# Printrhub_Rev_0_3.net
KiCad netlist of a schematic drawn in EAGLE
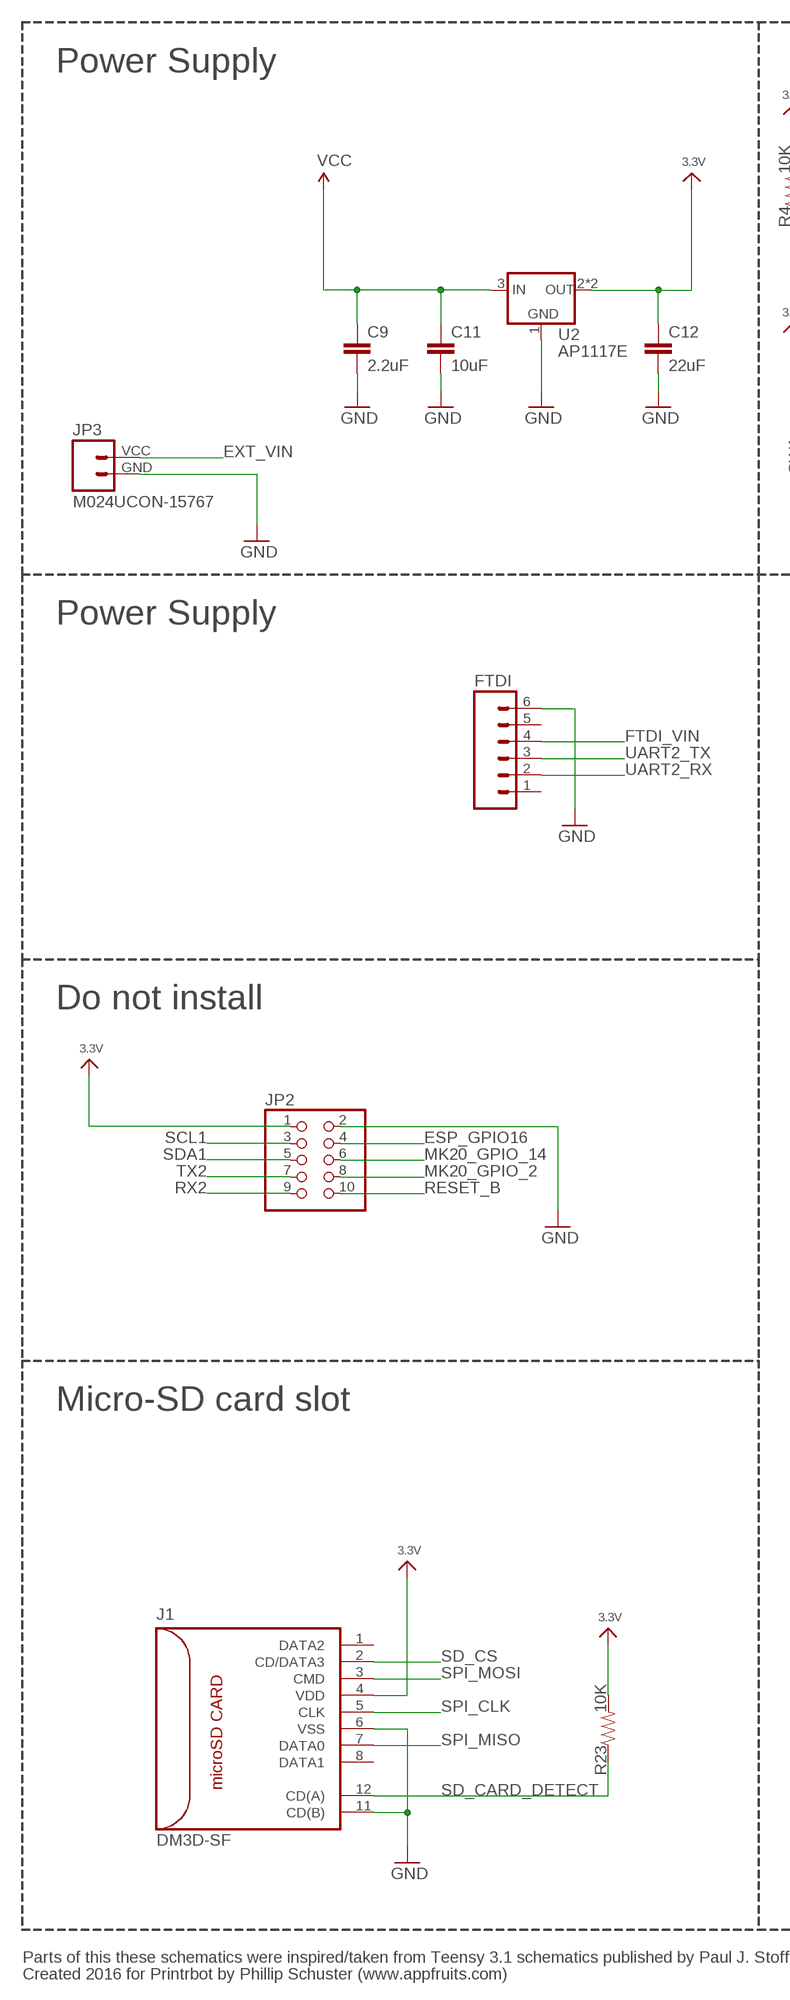
[diagram p0: schematic, sheet 1, part 1 of 2]
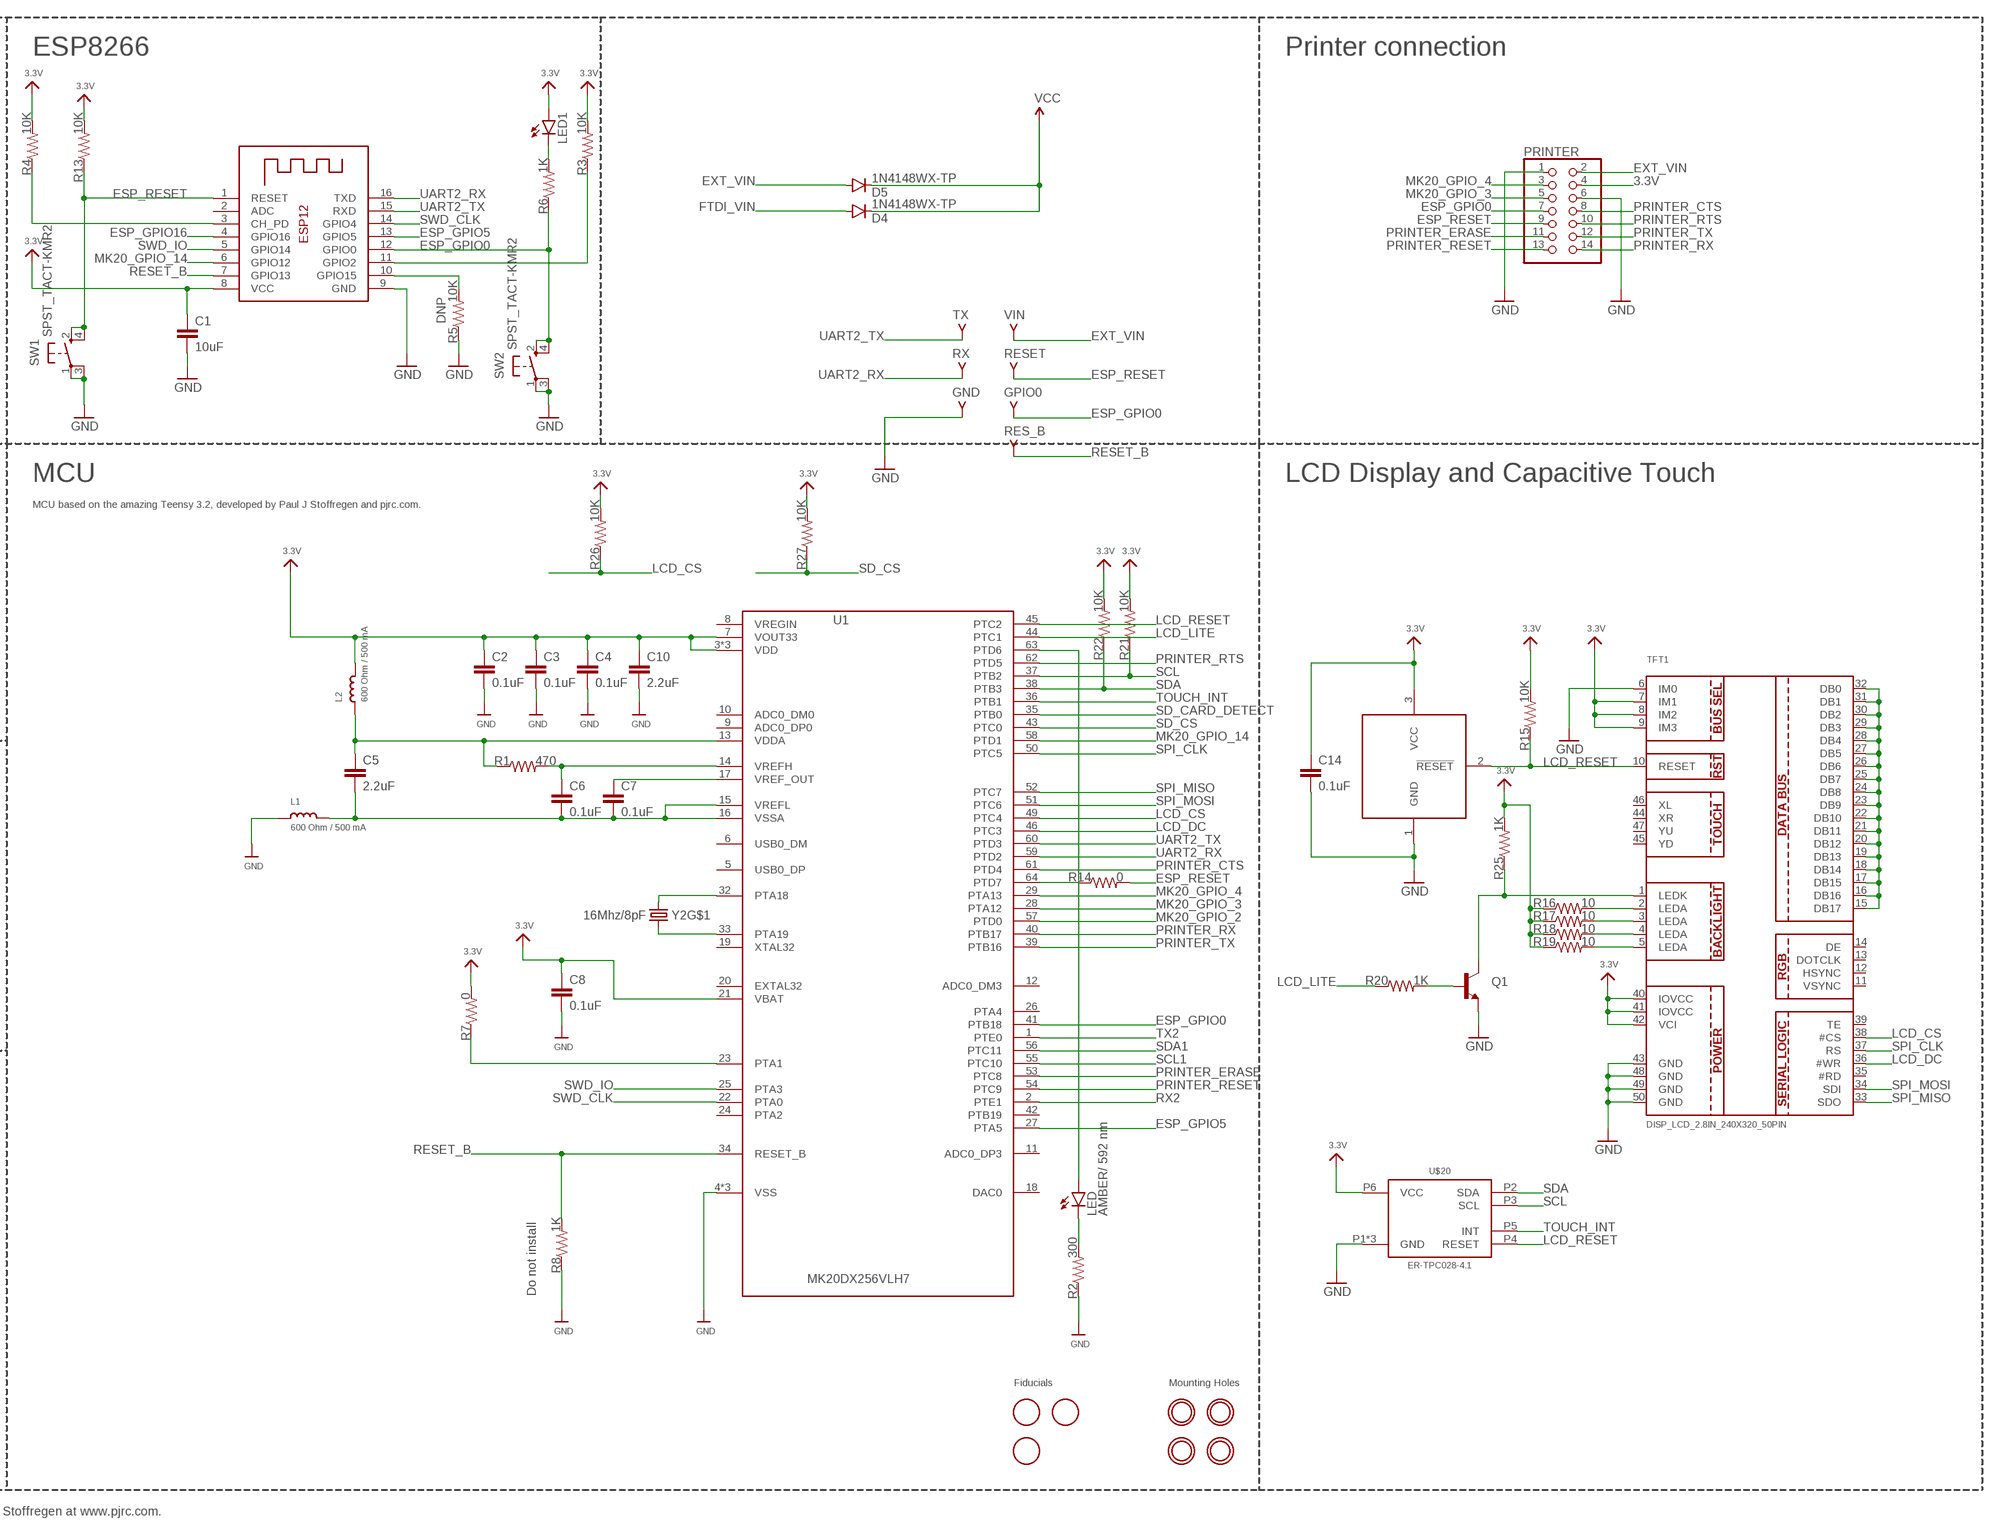
[diagram p1: schematic, sheet 1, part 2 of 2]

(export (version "E")
  (design (tool "Eeschema 10.0.6"))
  (components
    (comp (ref "C1")
      (value "10uF")
      (footprint "eagle-import:0603-CAP")
      (fields (field (name "MF") "Murata") (field (name "MPN") "GRM188R60J106ME47D"))
      (libsource (lib "eagle-import") (part "CAPACITOR-10UF"))
    )
    (comp (ref "C2")
      (value "0.1uF")
      (footprint "eagle-import:0603-CAP")
      (fields (field (name "MF") "Kemet") (field (name "MPN") "C0603C104J3RACTU"))
      (libsource (lib "eagle-import") (part "CAPACITOR-0.1UF"))
    )
    (comp (ref "C3")
      (value "0.1uF")
      (footprint "eagle-import:0603-CAP")
      (fields (field (name "MF") "Kemet") (field (name "MPN") "C0603C104J3RACTU"))
      (libsource (lib "eagle-import") (part "CAPACITOR-0.1UF"))
    )
    (comp (ref "C4")
      (value "0.1uF")
      (footprint "eagle-import:0603-CAP")
      (fields (field (name "MF") "Kemet") (field (name "MPN") "C0603C104J3RACTU"))
      (libsource (lib "eagle-import") (part "CAPACITOR-0.1UF"))
    )
    (comp (ref "C5")
      (value "2.2uF")
      (footprint "eagle-import:0603-CAP")
      (fields (field (name "MF") "Kemet") (field (name "MPN") "C0603C225K4PACTU"))
      (libsource (lib "eagle-import") (part "CAPACITOR-2.2UF"))
    )
    (comp (ref "C6")
      (value "0.1uF")
      (footprint "eagle-import:0603-CAP")
      (fields (field (name "MF") "Kemet") (field (name "MPN") "C0603C104J3RACTU"))
      (libsource (lib "eagle-import") (part "CAPACITOR-0.1UF"))
    )
    (comp (ref "C7")
      (value "0.1uF")
      (footprint "eagle-import:0603-CAP")
      (fields (field (name "MF") "Kemet") (field (name "MPN") "C0603C104J3RACTU"))
      (libsource (lib "eagle-import") (part "CAPACITOR-0.1UF"))
    )
    (comp (ref "C8")
      (value "0.1uF")
      (footprint "eagle-import:0603-CAP")
      (fields (field (name "MF") "Kemet") (field (name "MPN") "C0603C104J3RACTU"))
      (libsource (lib "eagle-import") (part "CAPACITOR-0.1UF"))
    )
    (comp (ref "C9")
      (value "2.2uF")
      (footprint "eagle-import:0603-CAP")
      (fields (field (name "MF") "Kemet") (field (name "MPN") "C0603C225K4PACTU"))
      (libsource (lib "eagle-import") (part "CAPACITOR-2.2UF"))
    )
    (comp (ref "C10")
      (value "2.2uF")
      (footprint "eagle-import:0603-CAP")
      (fields (field (name "MF") "Kemet") (field (name "MPN") "C0603C225K4PACTU"))
      (libsource (lib "eagle-import") (part "CAPACITOR-2.2UF"))
    )
    (comp (ref "C11")
      (value "10uF")
      (footprint "eagle-import:0603-CAP")
      (fields (field (name "MF") "Murata") (field (name "MPN") "GRM188R60J106ME47D"))
      (libsource (lib "eagle-import") (part "CAPACITOR-10UF"))
    )
    (comp (ref "C12")
      (value "22uF")
      (footprint "eagle-import:0603-CAP")
      (fields (field (name "MF") "Murata") (field (name "MPN") "GRM188R60J226MEA0D"))
      (libsource (lib "eagle-import") (part "CAPACITOR-22UF"))
    )
    (comp (ref "C14")
      (value "0.1uF")
      (footprint "eagle-import:0603-CAP")
      (fields (field (name "MF") "Kemet") (field (name "MPN") "C0603C104J3RACTU"))
      (libsource (lib "eagle-import") (part "CAPACITOR-0.1UF"))
    )
    (comp (ref "D4")
      (value "1N4148WX-TP")
      (footprint "eagle-import:SOD-323")
      (fields (field (name "MF") "Micro Commercial Co"))
      (libsource (lib "eagle-import") (part "DIODESOD"))
    )
    (comp (ref "D5")
      (value "1N4148WX-TP")
      (footprint "eagle-import:SOD-323")
      (fields (field (name "MF") "Micro Commercial Co"))
      (libsource (lib "eagle-import") (part "DIODESOD"))
    )
    (comp (ref "FTDI")
      (value "M06SMD-STRAIGHT-ALT")
      (footprint "eagle-import:1X06_SMD_STRAIGHT_ALT")
      (libsource (lib "eagle-import") (part "M06SMD-STRAIGHT-ALT"))
    )
    (comp (ref "GND")
      (value "TPV-SMD-18RN")
      (footprint "eagle-import:SMD-18RN")
      (libsource (lib "eagle-import") (part "TPV-SMD-18RN"))
    )
    (comp (ref "GPIO0")
      (value "TPV-SMD-18RN")
      (footprint "eagle-import:SMD-18RN")
      (libsource (lib "eagle-import") (part "TPV-SMD-18RN"))
    )
    (comp (ref "J1")
      (value "DM3D-SF")
      (footprint "eagle-import:DM3D-SF")
      (libsource (lib "eagle-import") (part "DM3D-SF"))
    )
    (comp (ref "JP2")
      (value "PINHD-2X5SMT")
      (footprint "eagle-import:2X05_SMT")
      (libsource (lib "eagle-import") (part "PINHD-2X5SMT"))
    )
    (comp (ref "JP3")
      (value "M024UCON-15767")
      (footprint "eagle-import:JST-2-SMD-VERT")
      (libsource (lib "eagle-import") (part "M024UCON-15767"))
    )
    (comp (ref "L1")
      (value "600 Ohm / 500 mA")
      (footprint "eagle-import:0603")
      (fields (field (name "MF") "Murata") (field (name "MPN") "BLM18AG601SN1D"))
      (libsource (lib "eagle-import") (part "INDUCTOR-0603_600OHM/500MA"))
    )
    (comp (ref "L2")
      (value "600 Ohm / 500 mA")
      (footprint "eagle-import:0603")
      (fields (field (name "MF") "Murata") (field (name "MPN") "BLM18AG601SN1D"))
      (libsource (lib "eagle-import") (part "INDUCTOR-0603_600OHM/500MA"))
    )
    (comp (ref "LED")
      (value "AMBER/ 592 nm")
      (footprint "eagle-import:LED-0603")
      (fields (field (name "MF") "Avago Technologies") (field (name "MPN") "HSMA-C190"))
      (libsource (lib "eagle-import") (part "LED-AMBER"))
    )
    (comp (ref "LED1")
      (value "LED-GREEN")
      (footprint "eagle-import:LED-0603")
      (fields (field (name "MF") "Avago") (field (name "MPN") "HSMG-C190"))
      (libsource (lib "eagle-import") (part "LED-GREEN"))
    )
    (comp (ref "PRINTER")
      (value "PINHD-2X7SMT")
      (footprint "eagle-import:2X07_SMT")
      (libsource (lib "eagle-import") (part "PINHD-2X7SMT"))
    )
    (comp (ref "Q1")
      (value "TRANSISTOR_NPNSOT23-3")
      (footprint "eagle-import:SOT23-3")
      (fields (field (name "MF") "ON Semiconductor") (field (name "MPN") "MMBT2222ALT1G"))
      (libsource (lib "eagle-import") (part "TRANSISTOR_NPNSOT23-3"))
    )
    (comp (ref "R1")
      (value "470")
      (footprint "eagle-import:0603-RES")
      (fields (field (name "MF") "Panasonic") (field (name "MPN") "ERJ-3GEYJ471V"))
      (libsource (lib "eagle-import") (part "RESISTOR-470"))
    )
    (comp (ref "R2")
      (value "300")
      (footprint "eagle-import:0603-RES")
      (libsource (lib "eagle-import") (part "RESISTOR0603"))
    )
    (comp (ref "R3")
      (value "10K")
      (footprint "eagle-import:0603-RES")
      (fields (field (name "MF") "Panasonic") (field (name "MPN") "ERJ-3GEYJ103V"))
      (libsource (lib "eagle-import") (part "RESISTOR-10K"))
    )
    (comp (ref "R4")
      (value "10K")
      (footprint "eagle-import:0603-RES")
      (fields (field (name "MF") "Panasonic") (field (name "MPN") "ERJ-3GEYJ103V"))
      (libsource (lib "eagle-import") (part "RESISTOR-10K"))
    )
    (comp (ref "R5")
      (value "10K")
      (footprint "eagle-import:0603-RES")
      (fields (field (name "MF") "Panasonic") (field (name "MPN") "ERJ-3GEYJ103V"))
      (libsource (lib "eagle-import") (part "RESISTOR-10K"))
    )
    (comp (ref "R6")
      (value "1K")
      (footprint "eagle-import:0603-RES")
      (fields (field (name "MF") "Panasonic") (field (name "MPN") "ERJ-3GEYJ102V"))
      (libsource (lib "eagle-import") (part "RESISTOR-1K"))
    )
    (comp (ref "R7")
      (value "0")
      (footprint "eagle-import:0603-RES")
      (fields (field (name "MF") "Panasonic") (field (name "MPN") "ERJ-3GEY0R00V"))
      (libsource (lib "eagle-import") (part "RESISTOR-0"))
    )
    (comp (ref "R8")
      (value "1K")
      (footprint "eagle-import:0603-RES")
      (fields (field (name "MF") "Panasonic") (field (name "MPN") "ERJ-3GEYJ102V"))
      (libsource (lib "eagle-import") (part "RESISTOR-1K"))
    )
    (comp (ref "R13")
      (value "10K")
      (footprint "eagle-import:0603-RES")
      (fields (field (name "MF") "Panasonic") (field (name "MPN") "ERJ-3GEYJ103V"))
      (libsource (lib "eagle-import") (part "RESISTOR-10K"))
    )
    (comp (ref "R14")
      (value "0")
      (footprint "eagle-import:0603-RES")
      (fields (field (name "MF") "Panasonic") (field (name "MPN") "ERJ-3GEY0R00V"))
      (libsource (lib "eagle-import") (part "RESISTOR-0"))
    )
    (comp (ref "R15")
      (value "10K")
      (footprint "eagle-import:0603-RES")
      (fields (field (name "MF") "Panasonic") (field (name "MPN") "ERJ-3GEYJ103V"))
      (libsource (lib "eagle-import") (part "RESISTOR-10K"))
    )
    (comp (ref "R16")
      (value "10")
      (footprint "eagle-import:0603-RES")
      (fields (field (name "MF") "Panasonic") (field (name "MPN") "ERJ-3EKF10R0V"))
      (libsource (lib "eagle-import") (part "RESISTOR-10"))
    )
    (comp (ref "R17")
      (value "10")
      (footprint "eagle-import:0603-RES")
      (fields (field (name "MF") "Panasonic") (field (name "MPN") "ERJ-3EKF10R0V"))
      (libsource (lib "eagle-import") (part "RESISTOR-10"))
    )
    (comp (ref "R18")
      (value "10")
      (footprint "eagle-import:0603-RES")
      (fields (field (name "MF") "Panasonic") (field (name "MPN") "ERJ-3EKF10R0V"))
      (libsource (lib "eagle-import") (part "RESISTOR-10"))
    )
    (comp (ref "R19")
      (value "10")
      (footprint "eagle-import:0603-RES")
      (fields (field (name "MF") "Panasonic") (field (name "MPN") "ERJ-3EKF10R0V"))
      (libsource (lib "eagle-import") (part "RESISTOR-10"))
    )
    (comp (ref "R20")
      (value "1K")
      (footprint "eagle-import:0603-RES")
      (fields (field (name "MF") "Panasonic") (field (name "MPN") "ERJ-3GEYJ102V"))
      (libsource (lib "eagle-import") (part "RESISTOR-1K"))
    )
    (comp (ref "R21")
      (value "10K")
      (footprint "eagle-import:0603-RES")
      (fields (field (name "MF") "Panasonic") (field (name "MPN") "ERJ-3GEYJ103V"))
      (libsource (lib "eagle-import") (part "RESISTOR-10K"))
    )
    (comp (ref "R22")
      (value "10K")
      (footprint "eagle-import:0603-RES")
      (fields (field (name "MF") "Panasonic") (field (name "MPN") "ERJ-3GEYJ103V"))
      (libsource (lib "eagle-import") (part "RESISTOR-10K"))
    )
    (comp (ref "R23")
      (value "10K")
      (footprint "eagle-import:0603-RES")
      (fields (field (name "MF") "Panasonic") (field (name "MPN") "ERJ-3GEYJ103V"))
      (libsource (lib "eagle-import") (part "RESISTOR-10K"))
    )
    (comp (ref "R25")
      (value "1K")
      (footprint "eagle-import:0603-RES")
      (fields (field (name "MF") "Panasonic") (field (name "MPN") "ERJ-3GEYJ102V"))
      (libsource (lib "eagle-import") (part "RESISTOR-1K"))
    )
    (comp (ref "R26")
      (value "10K")
      (footprint "eagle-import:0603-RES")
      (fields (field (name "MF") "Panasonic") (field (name "MPN") "ERJ-3GEYJ103V"))
      (libsource (lib "eagle-import") (part "RESISTOR-10K"))
    )
    (comp (ref "R27")
      (value "10K")
      (footprint "eagle-import:0603-RES")
      (fields (field (name "MF") "Panasonic") (field (name "MPN") "ERJ-3GEYJ103V"))
      (libsource (lib "eagle-import") (part "RESISTOR-10K"))
    )
    (comp (ref "RESET")
      (value "TPV-SMD-18RN")
      (footprint "eagle-import:SMD-18RN")
      (libsource (lib "eagle-import") (part "TPV-SMD-18RN"))
    )
    (comp (ref "RES_B")
      (value "TPV-SMD-18RN")
      (footprint "eagle-import:SMD-18RN")
      (libsource (lib "eagle-import") (part "TPV-SMD-18RN"))
    )
    (comp (ref "RX")
      (value "TPV-SMD-18RN")
      (footprint "eagle-import:SMD-18RN")
      (libsource (lib "eagle-import") (part "TPV-SMD-18RN"))
    )
    (comp (ref "SW1")
      (value "SPST_TACT-KMR2")
      (footprint "eagle-import:KMR2")
      (libsource (lib "eagle-import") (part "SPST_TACT-KMR2"))
    )
    (comp (ref "SW2")
      (value "SPST_TACT-KMR2")
      (footprint "eagle-import:KMR2")
      (libsource (lib "eagle-import") (part "SPST_TACT-KMR2"))
    )
    (comp (ref "TFT1")
      (value "DISP_LCD_2.8IN_240X320_50PIN")
      (footprint "eagle-import:TFT_2.83IN_240X320_50PIN")
      (libsource (lib "eagle-import") (part "DISP_LCD_2.8IN_240X320_50PIN"))
    )
    (comp (ref "TX")
      (value "TPV-SMD-18RN")
      (footprint "eagle-import:SMD-18RN")
      (libsource (lib "eagle-import") (part "TPV-SMD-18RN"))
    )
    (comp (ref "U$15")
      (value "MOUNTINGHOLE2.0")
      (footprint "eagle-import:MOUNTINGHOLE_2.0_PLATED")
      (libsource (lib "eagle-import") (part "MOUNTINGHOLE2.0"))
    )
    (comp (ref "U$16")
      (value "MOUNTINGHOLE2.0")
      (footprint "eagle-import:MOUNTINGHOLE_2.0_PLATED")
      (libsource (lib "eagle-import") (part "MOUNTINGHOLE2.0"))
    )
    (comp (ref "U$17")
      (value "MOUNTINGHOLE2.0")
      (footprint "eagle-import:MOUNTINGHOLE_2.0_PLATED")
      (libsource (lib "eagle-import") (part "MOUNTINGHOLE2.0"))
    )
    (comp (ref "U$18")
      (value "MOUNTINGHOLE2.0")
      (footprint "eagle-import:MOUNTINGHOLE_2.0_PLATED")
      (libsource (lib "eagle-import") (part "MOUNTINGHOLE2.0"))
    )
    (comp (ref "U$20")
      (value "ER-TPC028-4.1")
      (footprint "eagle-import:ER-CON06HB-1")
      (libsource (lib "eagle-import") (part "ER-TPC028-4.1"))
    )
    (comp (ref "U$38")
      (value "FIDUCIAL")
      (footprint "eagle-import:FIDUCIAL_1MM")
      (libsource (lib "eagle-import") (part "FIDUCIAL"))
    )
    (comp (ref "U$39")
      (value "FIDUCIAL")
      (footprint "eagle-import:FIDUCIAL_1MM")
      (libsource (lib "eagle-import") (part "FIDUCIAL"))
    )
    (comp (ref "U$40")
      (value "FIDUCIAL")
      (footprint "eagle-import:FIDUCIAL_1MM")
      (libsource (lib "eagle-import") (part "FIDUCIAL"))
    )
    (comp (ref "U1")
      (value "MK20DX256VLH7")
      (footprint "eagle-import:MK20DX256VLH7")
      (fields (field (name "MF") "Freescale"))
      (libsource (lib "eagle-import") (part "MK20DX256VLH7"))
    )
    (comp (ref "U2")
      (value "AP1117E")
      (footprint "eagle-import:SOT223")
      (libsource (lib "eagle-import") (part "AP1117E"))
    )
    (comp (ref "U3")
      (value "MAX308-SOT23")
      (footprint "eagle-import:SOT23")
      (libsource (lib "eagle-import") (part "MAX308-SOT23"))
    )
    (comp (ref "VIN")
      (value "TPV-SMD-18RN")
      (footprint "eagle-import:SMD-18RN")
      (libsource (lib "eagle-import") (part "TPV-SMD-18RN"))
    )
    (comp (ref "X1")
      (value "ESP-12")
      (footprint "eagle-import:ESP-12")
      (libsource (lib "eagle-import") (part "ESP-12"))
    )
    (comp (ref "Y2")
      (value "16Mhz/8pF")
      (footprint "eagle-import:CRYSTAL-SMD-5X3")
      (fields (field (name "MF") "ECS") (field (name "MPN") "ECS-160-8-30B-CKM"))
      (libsource (lib "eagle-import") (part "CRYSTAL/SMD-5X3-GND16MHZ/8PF"))
    )
  )
  (nets
    (net (code "1") (name "/ESP_GPIO0") (class "Default")
      (node (ref "GPIO0") (pin "TP") (pinfunction "TP_TP") (pintype "passive"))
      (node (ref "PRINTER") (pin "7") (pinfunction "7_7") (pintype "passive"))
      (node (ref "R6") (pin "1") (pinfunction "1_1") (pintype "passive"))
      (node (ref "SW2") (pin "2") (pinfunction "S_2") (pintype "passive"))
      (node (ref "SW2") (pin "4") (pinfunction "S1_4") (pintype "passive"))
      (node (ref "U1") (pin "41") (pinfunction "PTB18_41") (pintype "bidirectional"))
      (node (ref "X1") (pin "12") (pinfunction "GPIO0_12") (pintype "bidirectional"))
    )
    (net (code "2") (name "/ESP_GPIO5") (class "Default")
      (node (ref "U1") (pin "27") (pinfunction "PTA5_27") (pintype "bidirectional"))
      (node (ref "X1") (pin "13") (pinfunction "GPIO5_13") (pintype "bidirectional"))
    )
    (net (code "3") (name "/ESP_GPIO16") (class "Default")
      (node (ref "JP2") (pin "4") (pinfunction "4_4") (pintype "passive"))
      (node (ref "X1") (pin "4") (pinfunction "GPIO16_4") (pintype "bidirectional"))
    )
    (net (code "4") (name "/ESP_RESET") (class "Default")
      (node (ref "PRINTER") (pin "9") (pinfunction "9_9") (pintype "passive"))
      (node (ref "R13") (pin "1") (pinfunction "1_1") (pintype "passive"))
      (node (ref "R14") (pin "2") (pinfunction "2_2") (pintype "passive"))
      (node (ref "RESET") (pin "TP") (pinfunction "TP_TP") (pintype "passive"))
      (node (ref "SW1") (pin "2") (pinfunction "S_2") (pintype "passive"))
      (node (ref "SW1") (pin "4") (pinfunction "S1_4") (pintype "passive"))
      (node (ref "X1") (pin "1") (pinfunction "RESET_1") (pintype "input"))
    )
    (net (code "5") (name "/EXT_VIN") (class "Default")
      (node (ref "D5") (pin "A") (pinfunction "A_A") (pintype "passive"))
      (node (ref "JP3") (pin "VCC") (pinfunction "2_VCC") (pintype "passive"))
      (node (ref "PRINTER") (pin "2") (pinfunction "2_2") (pintype "passive"))
      (node (ref "VIN") (pin "TP") (pinfunction "TP_TP") (pintype "passive"))
    )
    (net (code "6") (name "/FTDI_VIN") (class "Default")
      (node (ref "D4") (pin "A") (pinfunction "A_A") (pintype "passive"))
      (node (ref "FTDI") (pin "4") (pinfunction "4_4") (pintype "passive"))
    )
    (net (code "7") (name "/LCD_CS") (class "Default")
      (node (ref "R26") (pin "1") (pinfunction "1_1") (pintype "passive"))
      (node (ref "TFT1") (pin "38") (pinfunction "#CS_38") (pintype "bidirectional"))
      (node (ref "U1") (pin "49") (pinfunction "PTC4_49") (pintype "bidirectional"))
    )
    (net (code "8") (name "/LCD_DC") (class "Default")
      (node (ref "TFT1") (pin "36") (pinfunction "#WR_36") (pintype "bidirectional"))
      (node (ref "U1") (pin "46") (pinfunction "PTC3_46") (pintype "bidirectional"))
    )
    (net (code "9") (name "/LCD_LITE") (class "Default")
      (node (ref "R20") (pin "1") (pinfunction "1_1") (pintype "passive"))
      (node (ref "U1") (pin "44") (pinfunction "PTC1_44") (pintype "bidirectional"))
    )
    (net (code "10") (name "/LCD_RESET") (class "Default")
      (node (ref "R15") (pin "1") (pinfunction "1_1") (pintype "passive"))
      (node (ref "TFT1") (pin "10") (pinfunction "RESET_10") (pintype "bidirectional"))
      (node (ref "U$20") (pin "P4") (pinfunction "RESET_P4") (pintype "bidirectional"))
      (node (ref "U1") (pin "45") (pinfunction "PTC2_45") (pintype "bidirectional"))
      (node (ref "U3") (pin "2") (pinfunction "~{RESET}_2") (pintype "bidirectional"))
    )
    (net (code "11") (name "/MK20_GPIO_2") (class "Default")
      (node (ref "JP2") (pin "8") (pinfunction "8_8") (pintype "passive"))
      (node (ref "U1") (pin "57") (pinfunction "PTD0_57") (pintype "bidirectional"))
    )
    (net (code "12") (name "/MK20_GPIO_3") (class "Default")
      (node (ref "PRINTER") (pin "5") (pinfunction "5_5") (pintype "passive"))
      (node (ref "U1") (pin "28") (pinfunction "PTA12_28") (pintype "bidirectional"))
    )
    (net (code "13") (name "/MK20_GPIO_4") (class "Default")
      (node (ref "PRINTER") (pin "3") (pinfunction "3_3") (pintype "passive"))
      (node (ref "U1") (pin "29") (pinfunction "PTA13_29") (pintype "bidirectional"))
    )
    (net (code "14") (name "/MK20_GPIO_14") (class "Default")
      (node (ref "JP2") (pin "6") (pinfunction "6_6") (pintype "passive"))
      (node (ref "U1") (pin "58") (pinfunction "PTD1_58") (pintype "bidirectional"))
      (node (ref "X1") (pin "6") (pinfunction "GPIO12_6") (pintype "bidirectional"))
    )
    (net (code "15") (name "/PRINTER_CTS") (class "Default")
      (node (ref "PRINTER") (pin "8") (pinfunction "8_8") (pintype "passive"))
      (node (ref "U1") (pin "61") (pinfunction "PTD4_61") (pintype "bidirectional"))
    )
    (net (code "16") (name "/PRINTER_ERASE") (class "Default")
      (node (ref "PRINTER") (pin "11") (pinfunction "11_11") (pintype "passive"))
      (node (ref "U1") (pin "53") (pinfunction "PTC8_53") (pintype "bidirectional"))
    )
    (net (code "17") (name "/PRINTER_RESET") (class "Default")
      (node (ref "PRINTER") (pin "13") (pinfunction "13_13") (pintype "passive"))
      (node (ref "U1") (pin "54") (pinfunction "PTC9_54") (pintype "bidirectional"))
    )
    (net (code "18") (name "/PRINTER_RTS") (class "Default")
      (node (ref "PRINTER") (pin "10") (pinfunction "10_10") (pintype "passive"))
      (node (ref "U1") (pin "62") (pinfunction "PTD5_62") (pintype "bidirectional"))
    )
    (net (code "19") (name "/PRINTER_RX") (class "Default")
      (node (ref "PRINTER") (pin "14") (pinfunction "14_14") (pintype "passive"))
      (node (ref "U1") (pin "40") (pinfunction "PTB17_40") (pintype "bidirectional"))
    )
    (net (code "20") (name "/PRINTER_TX") (class "Default")
      (node (ref "PRINTER") (pin "12") (pinfunction "12_12") (pintype "passive"))
      (node (ref "U1") (pin "39") (pinfunction "PTB16_39") (pintype "bidirectional"))
    )
    (net (code "21") (name "/RESET_B") (class "Default")
      (node (ref "JP2") (pin "10") (pinfunction "10_10") (pintype "passive"))
      (node (ref "R8") (pin "2") (pinfunction "2_2") (pintype "passive"))
      (node (ref "RES_B") (pin "TP") (pinfunction "TP_TP") (pintype "passive"))
      (node (ref "U1") (pin "34") (pinfunction "RESET_B_34") (pintype "bidirectional"))
      (node (ref "X1") (pin "7") (pinfunction "GPIO13_7") (pintype "bidirectional"))
    )
    (net (code "22") (name "/RX2") (class "Default")
      (node (ref "JP2") (pin "9") (pinfunction "9_9") (pintype "passive"))
      (node (ref "U1") (pin "2") (pinfunction "PTE1_2") (pintype "bidirectional"))
    )
    (net (code "23") (name "/SCL") (class "Default")
      (node (ref "R21") (pin "1") (pinfunction "1_1") (pintype "passive"))
      (node (ref "U$20") (pin "P3") (pinfunction "SCL_P3") (pintype "bidirectional"))
      (node (ref "U1") (pin "37") (pinfunction "PTB2_37") (pintype "bidirectional"))
    )
    (net (code "24") (name "/SCL1") (class "Default")
      (node (ref "JP2") (pin "3") (pinfunction "3_3") (pintype "passive"))
      (node (ref "U1") (pin "55") (pinfunction "PTC10_55") (pintype "bidirectional"))
    )
    (net (code "25") (name "/SDA") (class "Default")
      (node (ref "R22") (pin "1") (pinfunction "1_1") (pintype "passive"))
      (node (ref "U$20") (pin "P2") (pinfunction "SDA_P2") (pintype "bidirectional"))
      (node (ref "U1") (pin "38") (pinfunction "PTB3_38") (pintype "bidirectional"))
    )
    (net (code "26") (name "/SDA1") (class "Default")
      (node (ref "JP2") (pin "5") (pinfunction "5_5") (pintype "passive"))
      (node (ref "U1") (pin "56") (pinfunction "PTC11_56") (pintype "bidirectional"))
    )
    (net (code "27") (name "/SD_CARD_DETECT") (class "Default")
      (node (ref "J1") (pin "12") (pinfunction "CD(A)_12") (pintype "bidirectional"))
      (node (ref "R23") (pin "1") (pinfunction "1_1") (pintype "passive"))
      (node (ref "U1") (pin "35") (pinfunction "PTB0_35") (pintype "bidirectional"))
    )
    (net (code "28") (name "/SD_CS") (class "Default")
      (node (ref "J1") (pin "2") (pinfunction "CD/DATA3_2") (pintype "bidirectional"))
      (node (ref "R27") (pin "1") (pinfunction "1_1") (pintype "passive"))
      (node (ref "U1") (pin "43") (pinfunction "PTC0_43") (pintype "bidirectional"))
    )
    (net (code "29") (name "/SPI_CLK") (class "Default")
      (node (ref "J1") (pin "5") (pinfunction "CLK_5") (pintype "bidirectional"))
      (node (ref "TFT1") (pin "37") (pinfunction "RS_37") (pintype "bidirectional"))
      (node (ref "U1") (pin "50") (pinfunction "PTC5_50") (pintype "bidirectional"))
    )
    (net (code "30") (name "/SPI_MISO") (class "Default")
      (node (ref "J1") (pin "7") (pinfunction "DATA0_7") (pintype "bidirectional"))
      (node (ref "TFT1") (pin "33") (pinfunction "SDO_33") (pintype "bidirectional"))
      (node (ref "U1") (pin "52") (pinfunction "PTC7_52") (pintype "bidirectional"))
    )
    (net (code "31") (name "/SPI_MOSI") (class "Default")
      (node (ref "J1") (pin "3") (pinfunction "CMD_3") (pintype "bidirectional"))
      (node (ref "TFT1") (pin "34") (pinfunction "SDI_34") (pintype "bidirectional"))
      (node (ref "U1") (pin "51") (pinfunction "PTC6_51") (pintype "bidirectional"))
    )
    (net (code "32") (name "/SWD_CLK") (class "Default")
      (node (ref "U1") (pin "22") (pinfunction "PTA0_22") (pintype "bidirectional"))
      (node (ref "X1") (pin "14") (pinfunction "GPIO4_14") (pintype "bidirectional"))
    )
    (net (code "33") (name "/SWD_IO") (class "Default")
      (node (ref "U1") (pin "25") (pinfunction "PTA3_25") (pintype "bidirectional"))
      (node (ref "X1") (pin "5") (pinfunction "GPIO14_5") (pintype "bidirectional"))
    )
    (net (code "34") (name "/TOUCH_INT") (class "Default")
      (node (ref "U$20") (pin "P5") (pinfunction "INT_P5") (pintype "bidirectional"))
      (node (ref "U1") (pin "36") (pinfunction "PTB1_36") (pintype "bidirectional"))
    )
    (net (code "35") (name "/TX2") (class "Default")
      (node (ref "JP2") (pin "7") (pinfunction "7_7") (pintype "passive"))
      (node (ref "U1") (pin "1") (pinfunction "PTE0_1") (pintype "bidirectional"))
    )
    (net (code "36") (name "/UART2_RX") (class "Default")
      (node (ref "FTDI") (pin "2") (pinfunction "2_2") (pintype "passive"))
      (node (ref "RX") (pin "TP") (pinfunction "TP_TP") (pintype "passive"))
      (node (ref "U1") (pin "59") (pinfunction "PTD2_59") (pintype "bidirectional"))
      (node (ref "X1") (pin "16") (pinfunction "TXD_16") (pintype "output"))
    )
    (net (code "37") (name "/UART2_TX") (class "Default")
      (node (ref "FTDI") (pin "3") (pinfunction "3_3") (pintype "passive"))
      (node (ref "TX") (pin "TP") (pinfunction "TP_TP") (pintype "passive"))
      (node (ref "U1") (pin "60") (pinfunction "PTD3_60") (pintype "bidirectional"))
      (node (ref "X1") (pin "15") (pinfunction "RXD_15") (pintype "input"))
    )
    (net (code "38") (name "3.3V") (class "Default")
      (node (ref "C1") (pin "1") (pinfunction "1_1") (pintype "passive"))
      (node (ref "C10") (pin "1") (pinfunction "1_1") (pintype "passive"))
      (node (ref "C12") (pin "1") (pinfunction "1_1") (pintype "passive"))
      (node (ref "C14") (pin "1") (pinfunction "1_1") (pintype "passive"))
      (node (ref "C2") (pin "1") (pinfunction "1_1") (pintype "passive"))
      (node (ref "C3") (pin "1") (pinfunction "1_1") (pintype "passive"))
      (node (ref "C4") (pin "1") (pinfunction "1_1") (pintype "passive"))
      (node (ref "C8") (pin "1") (pinfunction "1_1") (pintype "passive"))
      (node (ref "J1") (pin "4") (pinfunction "VDD_4") (pintype "power_in"))
      (node (ref "JP2") (pin "1") (pinfunction "1_1") (pintype "passive"))
      (node (ref "L2") (pin "2") (pinfunction "2_2") (pintype "passive"))
      (node (ref "LED1") (pin "A") (pinfunction "A_A") (pintype "passive"))
      (node (ref "PRINTER") (pin "4") (pinfunction "4_4") (pintype "passive"))
      (node (ref "R13") (pin "2") (pinfunction "2_2") (pintype "passive"))
      (node (ref "R15") (pin "2") (pinfunction "2_2") (pintype "passive"))
      (node (ref "R16") (pin "1") (pinfunction "1_1") (pintype "passive"))
      (node (ref "R17") (pin "1") (pinfunction "1_1") (pintype "passive"))
      (node (ref "R18") (pin "1") (pinfunction "1_1") (pintype "passive"))
      (node (ref "R19") (pin "1") (pinfunction "1_1") (pintype "passive"))
      (node (ref "R21") (pin "2") (pinfunction "2_2") (pintype "passive"))
      (node (ref "R22") (pin "2") (pinfunction "2_2") (pintype "passive"))
      (node (ref "R23") (pin "2") (pinfunction "2_2") (pintype "passive"))
      (node (ref "R25") (pin "2") (pinfunction "2_2") (pintype "passive"))
      (node (ref "R26") (pin "2") (pinfunction "2_2") (pintype "passive"))
      (node (ref "R27") (pin "2") (pinfunction "2_2") (pintype "passive"))
      (node (ref "R3") (pin "2") (pinfunction "2_2") (pintype "passive"))
      (node (ref "R4") (pin "2") (pinfunction "2_2") (pintype "passive"))
      (node (ref "R7") (pin "2") (pinfunction "2_2") (pintype "passive"))
      (node (ref "TFT1") (pin "40") (pinfunction "IOVCC_40") (pintype "bidirectional"))
      (node (ref "TFT1") (pin "41") (pinfunction "IOVCC_41") (pintype "bidirectional"))
      (node (ref "TFT1") (pin "42") (pinfunction "VCI_42") (pintype "bidirectional"))
      (node (ref "TFT1") (pin "7") (pinfunction "IM1_7") (pintype "bidirectional"))
      (node (ref "TFT1") (pin "8") (pinfunction "IM2_8") (pintype "bidirectional"))
      (node (ref "TFT1") (pin "9") (pinfunction "IM3_9") (pintype "bidirectional"))
      (node (ref "U$20") (pin "P6") (pinfunction "VCC_P6") (pintype "bidirectional"))
      (node (ref "U1") (pin "21") (pinfunction "VBAT_21") (pintype "bidirectional"))
      (node (ref "U1") (pin "3") (pinfunction "VDD_3") (pintype "bidirectional"))
      (node (ref "U1") (pin "30") (pinfunction "VDD_30") (pintype "bidirectional"))
      (node (ref "U1") (pin "48") (pinfunction "VDD_48") (pintype "bidirectional"))
      (node (ref "U1") (pin "7") (pinfunction "VOUT33_7") (pintype "bidirectional"))
      (node (ref "U2") (pin "2") (pinfunction "OUT_2") (pintype "passive"))
      (node (ref "U2") (pin "4") (pinfunction "OUT_4") (pintype "passive"))
      (node (ref "U3") (pin "3") (pinfunction "VCC_3") (pintype "bidirectional"))
      (node (ref "X1") (pin "8") (pinfunction "VCC_8") (pintype "power_in"))
    )
    (net (code "39") (name "GND") (class "Default")
      (node (ref "C1") (pin "2") (pinfunction "2_2") (pintype "passive"))
      (node (ref "C10") (pin "2") (pinfunction "2_2") (pintype "passive"))
      (node (ref "C11") (pin "2") (pinfunction "2_2") (pintype "passive"))
      (node (ref "C12") (pin "2") (pinfunction "2_2") (pintype "passive"))
      (node (ref "C14") (pin "2") (pinfunction "2_2") (pintype "passive"))
      (node (ref "C2") (pin "2") (pinfunction "2_2") (pintype "passive"))
      (node (ref "C3") (pin "2") (pinfunction "2_2") (pintype "passive"))
      (node (ref "C4") (pin "2") (pinfunction "2_2") (pintype "passive"))
      (node (ref "C8") (pin "2") (pinfunction "2_2") (pintype "passive"))
      (node (ref "C9") (pin "2") (pinfunction "2_2") (pintype "passive"))
      (node (ref "FTDI") (pin "6") (pinfunction "6_6") (pintype "passive"))
      (node (ref "GND") (pin "TP") (pinfunction "TP_TP") (pintype "passive"))
      (node (ref "J1") (pin "11") (pinfunction "CD(B)_11") (pintype "bidirectional"))
      (node (ref "J1") (pin "6") (pinfunction "VSS_6") (pintype "power_in"))
      (node (ref "JP2") (pin "2") (pinfunction "2_2") (pintype "passive"))
      (node (ref "JP3") (pin "GND") (pinfunction "1_GND") (pintype "passive"))
      (node (ref "L1") (pin "1") (pinfunction "1_1") (pintype "passive"))
      (node (ref "PRINTER") (pin "1") (pinfunction "1_1") (pintype "passive"))
      (node (ref "PRINTER") (pin "6") (pinfunction "6_6") (pintype "passive"))
      (node (ref "Q1") (pin "2") (pinfunction "E_2") (pintype "passive"))
      (node (ref "R2") (pin "1") (pinfunction "1_1") (pintype "passive"))
      (node (ref "R5") (pin "1") (pinfunction "1_1") (pintype "passive"))
      (node (ref "R8") (pin "1") (pinfunction "1_1") (pintype "passive"))
      (node (ref "SW1") (pin "1") (pinfunction "P_1") (pintype "passive"))
      (node (ref "SW1") (pin "3") (pinfunction "P1_3") (pintype "passive"))
      (node (ref "SW2") (pin "1") (pinfunction "P_1") (pintype "passive"))
      (node (ref "SW2") (pin "3") (pinfunction "P1_3") (pintype "passive"))
      (node (ref "TFT1") (pin "43") (pinfunction "GND_43") (pintype "bidirectional"))
      (node (ref "TFT1") (pin "48") (pinfunction "GND_48") (pintype "bidirectional"))
      (node (ref "TFT1") (pin "49") (pinfunction "GND_49") (pintype "bidirectional"))
      (node (ref "TFT1") (pin "50") (pinfunction "GND_50") (pintype "bidirectional"))
      (node (ref "TFT1") (pin "6") (pinfunction "IM0_6") (pintype "bidirectional"))
      (node (ref "U$20") (pin "P1") (pinfunction "GND_P1") (pintype "bidirectional"))
      (node (ref "U$20") (pin "PAD@0") (pinfunction "GND_PAD@0") (pintype "bidirectional"))
      (node (ref "U$20") (pin "PAD@1") (pinfunction "GND_PAD@1") (pintype "bidirectional"))
      (node (ref "U1") (pin "31") (pinfunction "VSS_31") (pintype "bidirectional"))
      (node (ref "U1") (pin "4") (pinfunction "VSS_4") (pintype "bidirectional"))
      (node (ref "U1") (pin "47") (pinfunction "VSS_47") (pintype "bidirectional"))
      (node (ref "U2") (pin "1") (pinfunction "GND_1") (pintype "input"))
      (node (ref "U3") (pin "1") (pinfunction "GND_1") (pintype "bidirectional"))
      (node (ref "X1") (pin "9") (pinfunction "GND_9") (pintype "power_in"))
    )
    (net (code "40") (name "Net-(LED-PadC)") (class "Default")
      (node (ref "LED") (pin "C") (pinfunction "C_C") (pintype "passive"))
      (node (ref "R2") (pin "2") (pinfunction "2_2") (pintype "passive"))
    )
    (net (code "41") (name "Net-(LED1-PadC)") (class "Default")
      (node (ref "LED1") (pin "C") (pinfunction "C_C") (pintype "passive"))
      (node (ref "R6") (pin "2") (pinfunction "2_2") (pintype "passive"))
    )
    (net (code "42") (name "Net-(Q1-B)") (class "Default")
      (node (ref "Q1") (pin "1") (pinfunction "B_1") (pintype "passive"))
      (node (ref "R20") (pin "2") (pinfunction "2_2") (pintype "passive"))
    )
    (net (code "43") (name "Net-(Q1-C)") (class "Default")
      (node (ref "Q1") (pin "3") (pinfunction "C_3") (pintype "passive"))
      (node (ref "R25") (pin "1") (pinfunction "1_1") (pintype "passive"))
      (node (ref "TFT1") (pin "1") (pinfunction "LEDK_1") (pintype "bidirectional"))
    )
    (net (code "44") (name "Net-(R16-Pad2)") (class "Default")
      (node (ref "R16") (pin "2") (pinfunction "2_2") (pintype "passive"))
      (node (ref "TFT1") (pin "2") (pinfunction "LEDA_2") (pintype "bidirectional"))
    )
    (net (code "45") (name "Net-(R17-Pad2)") (class "Default")
      (node (ref "R17") (pin "2") (pinfunction "2_2") (pintype "passive"))
      (node (ref "TFT1") (pin "3") (pinfunction "LEDA_3") (pintype "bidirectional"))
    )
    (net (code "46") (name "Net-(R18-Pad2)") (class "Default")
      (node (ref "R18") (pin "2") (pinfunction "2_2") (pintype "passive"))
      (node (ref "TFT1") (pin "4") (pinfunction "LEDA_4") (pintype "bidirectional"))
    )
    (net (code "47") (name "Net-(R19-Pad2)") (class "Default")
      (node (ref "R19") (pin "2") (pinfunction "2_2") (pintype "passive"))
      (node (ref "TFT1") (pin "5") (pinfunction "LEDA_5") (pintype "bidirectional"))
    )
    (net (code "48") (name "Net-(TFT1-DB0)") (class "Default")
      (node (ref "TFT1") (pin "15") (pinfunction "DB17_15") (pintype "bidirectional"))
      (node (ref "TFT1") (pin "16") (pinfunction "DB16_16") (pintype "bidirectional"))
      (node (ref "TFT1") (pin "17") (pinfunction "DB15_17") (pintype "bidirectional"))
      (node (ref "TFT1") (pin "18") (pinfunction "DB14_18") (pintype "bidirectional"))
      (node (ref "TFT1") (pin "19") (pinfunction "DB13_19") (pintype "bidirectional"))
      (node (ref "TFT1") (pin "20") (pinfunction "DB12_20") (pintype "bidirectional"))
      (node (ref "TFT1") (pin "21") (pinfunction "DB11_21") (pintype "bidirectional"))
      (node (ref "TFT1") (pin "22") (pinfunction "DB10_22") (pintype "bidirectional"))
      (node (ref "TFT1") (pin "23") (pinfunction "DB9_23") (pintype "bidirectional"))
      (node (ref "TFT1") (pin "24") (pinfunction "DB8_24") (pintype "bidirectional"))
      (node (ref "TFT1") (pin "25") (pinfunction "DB7_25") (pintype "bidirectional"))
      (node (ref "TFT1") (pin "26") (pinfunction "DB6_26") (pintype "bidirectional"))
      (node (ref "TFT1") (pin "27") (pinfunction "DB5_27") (pintype "bidirectional"))
      (node (ref "TFT1") (pin "28") (pinfunction "DB4_28") (pintype "bidirectional"))
      (node (ref "TFT1") (pin "29") (pinfunction "DB3_29") (pintype "bidirectional"))
      (node (ref "TFT1") (pin "30") (pinfunction "DB2_30") (pintype "bidirectional"))
      (node (ref "TFT1") (pin "31") (pinfunction "DB1_31") (pintype "bidirectional"))
      (node (ref "TFT1") (pin "32") (pinfunction "DB0_32") (pintype "bidirectional"))
    )
    (net (code "49") (name "Net-(U1-PTA1)") (class "Default")
      (node (ref "R7") (pin "1") (pinfunction "1_1") (pintype "passive"))
      (node (ref "U1") (pin "23") (pinfunction "PTA1_23") (pintype "bidirectional"))
    )
    (net (code "50") (name "Net-(U1-PTA18)") (class "Default")
      (node (ref "U1") (pin "32") (pinfunction "PTA18_32") (pintype "bidirectional"))
      (node (ref "Y2") (pin "3") (pinfunction "2_3") (pintype "passive"))
    )
    (net (code "51") (name "Net-(U1-PTA19)") (class "Default")
      (node (ref "U1") (pin "33") (pinfunction "PTA19_33") (pintype "bidirectional"))
      (node (ref "Y2") (pin "1") (pinfunction "1_1") (pintype "passive"))
    )
    (net (code "52") (name "Net-(U1-PTD6)") (class "Default")
      (node (ref "LED") (pin "A") (pinfunction "A_A") (pintype "passive"))
      (node (ref "U1") (pin "63") (pinfunction "PTD6_63") (pintype "bidirectional"))
    )
    (net (code "53") (name "Net-(U1-PTD7)") (class "Default")
      (node (ref "R14") (pin "1") (pinfunction "1_1") (pintype "passive"))
      (node (ref "U1") (pin "64") (pinfunction "PTD7_64") (pintype "bidirectional"))
    )
    (net (code "54") (name "Net-(U1-VDDA)") (class "Default")
      (node (ref "C5") (pin "1") (pinfunction "1_1") (pintype "passive"))
      (node (ref "L2") (pin "1") (pinfunction "1_1") (pintype "passive"))
      (node (ref "R1") (pin "1") (pinfunction "1_1") (pintype "passive"))
      (node (ref "U1") (pin "13") (pinfunction "VDDA_13") (pintype "bidirectional"))
    )
    (net (code "55") (name "Net-(U1-VREFH)") (class "Default")
      (node (ref "C6") (pin "1") (pinfunction "1_1") (pintype "passive"))
      (node (ref "R1") (pin "2") (pinfunction "2_2") (pintype "passive"))
      (node (ref "U1") (pin "14") (pinfunction "VREFH_14") (pintype "bidirectional"))
    )
    (net (code "56") (name "Net-(U1-VREFL)") (class "Default")
      (node (ref "C5") (pin "2") (pinfunction "2_2") (pintype "passive"))
      (node (ref "C6") (pin "2") (pinfunction "2_2") (pintype "passive"))
      (node (ref "C7") (pin "2") (pinfunction "2_2") (pintype "passive"))
      (node (ref "L1") (pin "2") (pinfunction "2_2") (pintype "passive"))
      (node (ref "U1") (pin "15") (pinfunction "VREFL_15") (pintype "bidirectional"))
      (node (ref "U1") (pin "16") (pinfunction "VSSA_16") (pintype "bidirectional"))
    )
    (net (code "57") (name "Net-(U1-VREF_OUT)") (class "Default")
      (node (ref "C7") (pin "1") (pinfunction "1_1") (pintype "passive"))
      (node (ref "U1") (pin "17") (pinfunction "VREF_OUT_17") (pintype "bidirectional"))
    )
    (net (code "58") (name "Net-(X1-CH_PD)") (class "Default")
      (node (ref "R4") (pin "1") (pinfunction "1_1") (pintype "passive"))
      (node (ref "X1") (pin "3") (pinfunction "CH_PD_3") (pintype "input"))
    )
    (net (code "59") (name "Net-(X1-GPIO2)") (class "Default")
      (node (ref "R3") (pin "1") (pinfunction "1_1") (pintype "passive"))
      (node (ref "X1") (pin "11") (pinfunction "GPIO2_11") (pintype "bidirectional"))
    )
    (net (code "60") (name "Net-(X1-GPIO15)") (class "Default")
      (node (ref "R5") (pin "2") (pinfunction "2_2") (pintype "passive"))
      (node (ref "X1") (pin "10") (pinfunction "GPIO15_10") (pintype "bidirectional"))
    )
    (net (code "61") (name "VCC") (class "Default")
      (node (ref "C11") (pin "1") (pinfunction "1_1") (pintype "passive"))
      (node (ref "C9") (pin "1") (pinfunction "1_1") (pintype "passive"))
      (node (ref "D4") (pin "C") (pinfunction "C_C") (pintype "passive"))
      (node (ref "D5") (pin "C") (pinfunction "C_C") (pintype "passive"))
      (node (ref "U2") (pin "3") (pinfunction "IN_3") (pintype "input"))
    )
    (net (code "62") (name "unconnected-(FTDI-Pad1)") (class "Default")
      (node (ref "FTDI") (pin "1") (pinfunction "1_1") (pintype "passive"))
    )
    (net (code "63") (name "unconnected-(FTDI-Pad5)") (class "Default")
      (node (ref "FTDI") (pin "5") (pinfunction "5_5") (pintype "passive"))
    )
    (net (code "64") (name "unconnected-(J1B-DATA1-Pad8)") (class "Default")
      (node (ref "J1") (pin "8") (pinfunction "DATA1_8") (pintype "bidirectional"))
    )
    (net (code "65") (name "unconnected-(J1B-DATA2-Pad1)") (class "Default")
      (node (ref "J1") (pin "1") (pinfunction "DATA2_1") (pintype "bidirectional"))
    )
    (net (code "66") (name "unconnected-(TFT1-#RD-Pad35)") (class "Default")
      (node (ref "TFT1") (pin "35") (pinfunction "#RD_35") (pintype "bidirectional"))
    )
    (net (code "67") (name "unconnected-(TFT1-DE-Pad14)") (class "Default")
      (node (ref "TFT1") (pin "14") (pinfunction "DE_14") (pintype "bidirectional"))
    )
    (net (code "68") (name "unconnected-(TFT1-DOTCLK-Pad13)") (class "Default")
      (node (ref "TFT1") (pin "13") (pinfunction "DOTCLK_13") (pintype "bidirectional"))
    )
    (net (code "69") (name "unconnected-(TFT1-HSYNC-Pad12)") (class "Default")
      (node (ref "TFT1") (pin "12") (pinfunction "HSYNC_12") (pintype "bidirectional"))
    )
    (net (code "70") (name "unconnected-(TFT1-TE-Pad39)") (class "Default")
      (node (ref "TFT1") (pin "39") (pinfunction "TE_39") (pintype "bidirectional"))
    )
    (net (code "71") (name "unconnected-(TFT1-VSYNC-Pad11)") (class "Default")
      (node (ref "TFT1") (pin "11") (pinfunction "VSYNC_11") (pintype "bidirectional"))
    )
    (net (code "72") (name "unconnected-(TFT1-XL-Pad46)") (class "Default")
      (node (ref "TFT1") (pin "46") (pinfunction "XL_46") (pintype "bidirectional"))
    )
    (net (code "73") (name "unconnected-(TFT1-XR-Pad44)") (class "Default")
      (node (ref "TFT1") (pin "44") (pinfunction "XR_44") (pintype "bidirectional"))
    )
    (net (code "74") (name "unconnected-(TFT1-YD-Pad45)") (class "Default")
      (node (ref "TFT1") (pin "45") (pinfunction "YD_45") (pintype "bidirectional"))
    )
    (net (code "75") (name "unconnected-(TFT1-YU-Pad47)") (class "Default")
      (node (ref "TFT1") (pin "47") (pinfunction "YU_47") (pintype "bidirectional"))
    )
    (net (code "76") (name "unconnected-(U1-ADC0_DM0-Pad10)") (class "Default")
      (node (ref "U1") (pin "10") (pinfunction "ADC0_DM0_10") (pintype "bidirectional"))
    )
    (net (code "77") (name "unconnected-(U1-ADC0_DM3-Pad12)") (class "Default")
      (node (ref "U1") (pin "12") (pinfunction "ADC0_DM3_12") (pintype "bidirectional"))
    )
    (net (code "78") (name "unconnected-(U1-ADC0_DP0-Pad9)") (class "Default")
      (node (ref "U1") (pin "9") (pinfunction "ADC0_DP0_9") (pintype "bidirectional"))
    )
    (net (code "79") (name "unconnected-(U1-ADC0_DP3-Pad11)") (class "Default")
      (node (ref "U1") (pin "11") (pinfunction "ADC0_DP3_11") (pintype "bidirectional"))
    )
    (net (code "80") (name "unconnected-(U1-DAC0-Pad18)") (class "Default")
      (node (ref "U1") (pin "18") (pinfunction "DAC0_18") (pintype "bidirectional"))
    )
    (net (code "81") (name "unconnected-(U1-EXTAL32-Pad20)") (class "Default")
      (node (ref "U1") (pin "20") (pinfunction "EXTAL32_20") (pintype "bidirectional"))
    )
    (net (code "82") (name "unconnected-(U1-PTA2-Pad24)") (class "Default")
      (node (ref "U1") (pin "24") (pinfunction "PTA2_24") (pintype "bidirectional"))
    )
    (net (code "83") (name "unconnected-(U1-PTA4-Pad26)") (class "Default")
      (node (ref "U1") (pin "26") (pinfunction "PTA4_26") (pintype "bidirectional"))
    )
    (net (code "84") (name "unconnected-(U1-PTB19-Pad42)") (class "Default")
      (node (ref "U1") (pin "42") (pinfunction "PTB19_42") (pintype "bidirectional"))
    )
    (net (code "85") (name "unconnected-(U1-USB0_DM-Pad6)") (class "Default")
      (node (ref "U1") (pin "6") (pinfunction "USB0_DM_6") (pintype "bidirectional"))
    )
    (net (code "86") (name "unconnected-(U1-USB0_DP-Pad5)") (class "Default")
      (node (ref "U1") (pin "5") (pinfunction "USB0_DP_5") (pintype "bidirectional"))
    )
    (net (code "87") (name "unconnected-(U1-VREGIN-Pad8)") (class "Default")
      (node (ref "U1") (pin "8") (pinfunction "VREGIN_8") (pintype "bidirectional"))
    )
    (net (code "88") (name "unconnected-(U1-XTAL32-Pad19)") (class "Default")
      (node (ref "U1") (pin "19") (pinfunction "XTAL32_19") (pintype "bidirectional"))
    )
    (net (code "89") (name "unconnected-(X1-ADC-Pad2)") (class "Default")
      (node (ref "X1") (pin "2") (pinfunction "ADC_2") (pintype "passive"))
    )
  )
)
